# altiumDesignerSchematic.net
KiCad netlist of a schematic drawn in Altium Designer
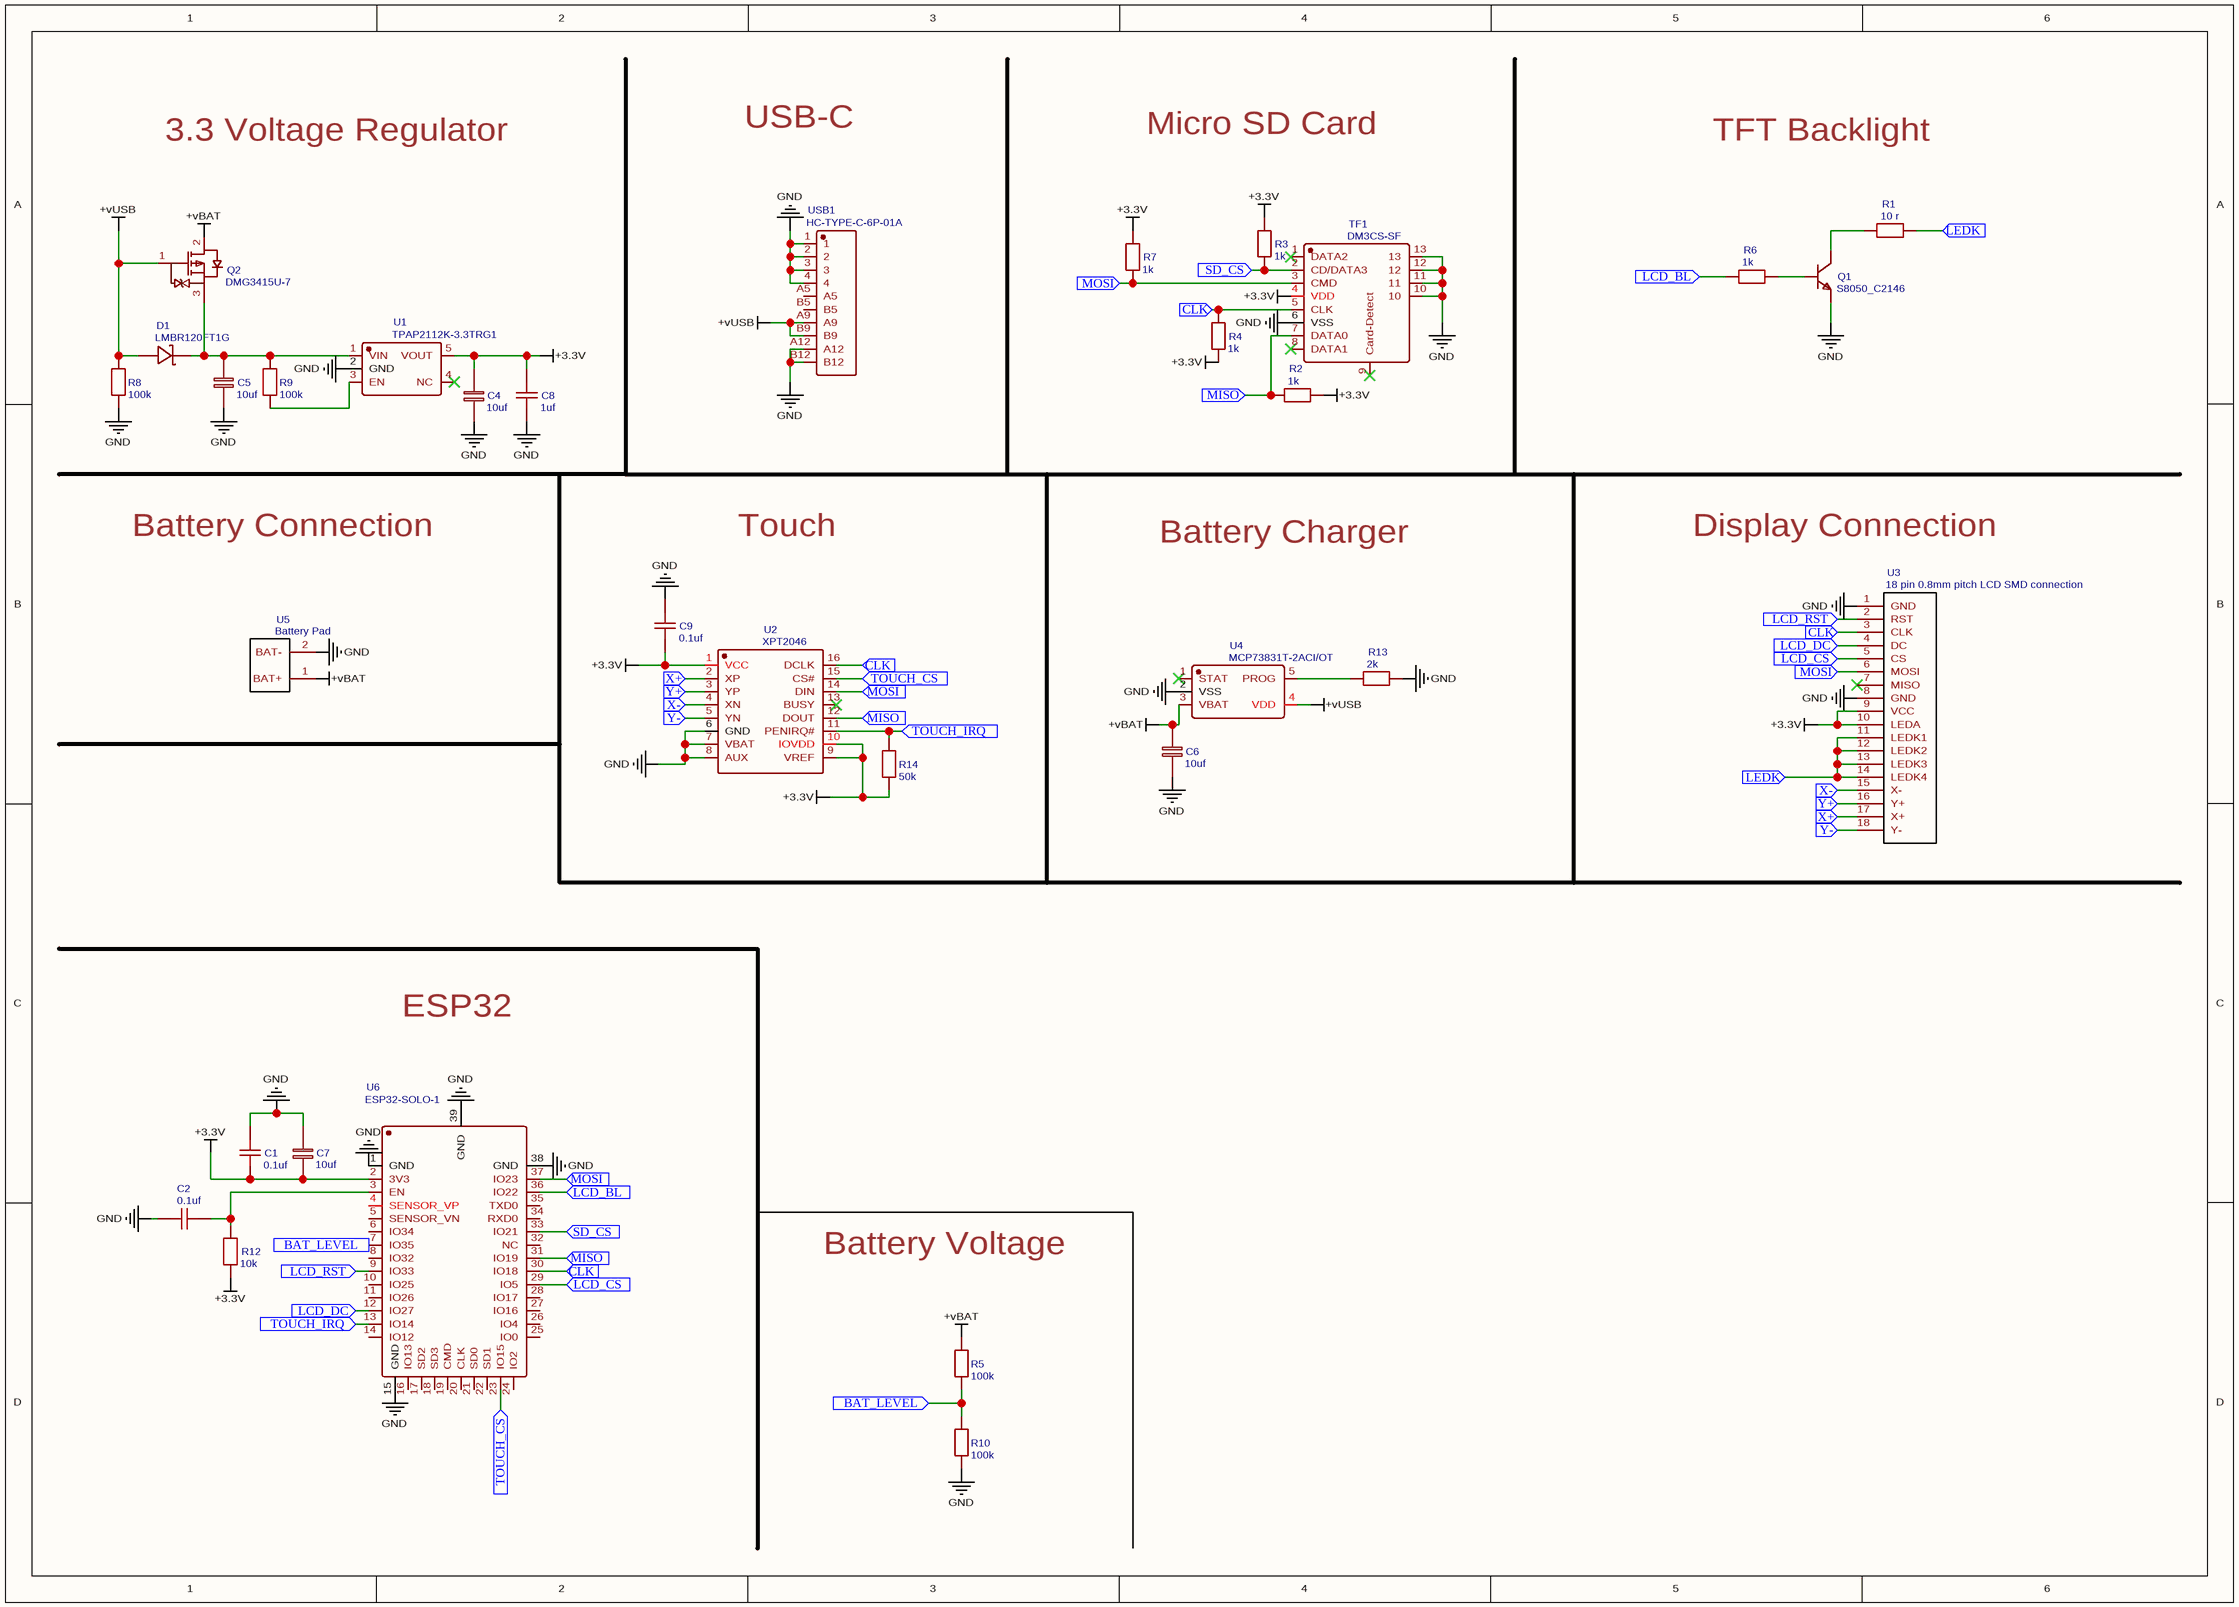
[diagram p0: altiumDesignerSchematic.schdoc]

(export (version "E")
  (design (tool "Eeschema 10.0.6"))
  (components
    (comp (ref "C1")
      (value "0.1uf")
      (fields (field (name "CONTRIBUTOR") "LCEDA_Lib"))
      (libsource (lib "altium-import") (part "root_1_0.1uf_"))
    )
    (comp (ref "C2")
      (value "0.1uf")
      (fields (field (name "CONTRIBUTOR") "LCEDA_Lib"))
      (libsource (lib "altium-import") (part "root_2_0.1uf_"))
    )
    (comp (ref "C4")
      (value "10uf")
      (fields (field (name "CONTRIBUTOR") "LCEDA_Lib"))
      (libsource (lib "altium-import") (part "root_1_10uf_"))
    )
    (comp (ref "C5")
      (value "10uf")
      (fields (field (name "CONTRIBUTOR") "LCEDA_Lib"))
      (libsource (lib "altium-import") (part "root_1_10uf_"))
    )
    (comp (ref "C6")
      (value "10uf")
      (fields (field (name "CONTRIBUTOR") "LCEDA_Lib"))
      (libsource (lib "altium-import") (part "root_1_10uf_"))
    )
    (comp (ref "C7")
      (value "10uf")
      (fields (field (name "CONTRIBUTOR") "LCEDA_Lib"))
      (libsource (lib "altium-import") (part "root_1_10uf_"))
    )
    (comp (ref "C8")
      (value "1uf")
      (fields (field (name "CONTRIBUTOR") "LCEDA_Lib"))
      (libsource (lib "altium-import") (part "root_1_1uf_"))
    )
    (comp (ref "C9")
      (value "0.1uf")
      (fields (field (name "CONTRIBUTOR") "LCEDA_Lib"))
      (libsource (lib "altium-import") (part "root_1_0.1uf_"))
    )
    (comp (ref "D1")
      (value "LMBR120FT1G")
      (fields (field (name "BOM_SUPPLIER PART") "C81143"))
      (libsource (lib "altium-import") (part "root_2_LMBR120FT1G_"))
    )
    (comp (ref "Q1")
      (value "S8050_C2146")
      (fields (field (name "BOM_MANUFACTURER PART") "S8050 J3Y") (field (name "BOM_SUPPLIER PART") "C2146"))
      (libsource (lib "altium-import") (part "root_0_S8050_C2146_"))
    )
    (comp (ref "Q2")
      (value "DMG3415U-7")
      (fields (field (name "BOM_SUPPLIER PART") "C96616") (field (name "CONTRIBUTOR") "LCSC"))
      (libsource (lib "altium-import") (part "root_0_DMG3415U-7_"))
    )
    (comp (ref "R1")
      (value "10 r")
      (fields (field (name "CONTRIBUTOR") "LCEDA_Lib"))
      (libsource (lib "altium-import") (part "root_0_10 r_"))
    )
    (comp (ref "R2")
      (value "1k")
      (fields (field (name "CONTRIBUTOR") "LCEDA_Lib"))
      (libsource (lib "altium-import") (part "root_0_1k_"))
    )
    (comp (ref "R3")
      (value "1k")
      (fields (field (name "CONTRIBUTOR") "LCEDA_Lib"))
      (libsource (lib "altium-import") (part "root_1_1k_"))
    )
    (comp (ref "R4")
      (value "1k")
      (fields (field (name "CONTRIBUTOR") "LCEDA_Lib"))
      (libsource (lib "altium-import") (part "root_1_1k_"))
    )
    (comp (ref "R5")
      (value "100k")
      (fields (field (name "CONTRIBUTOR") "LCEDA_Lib"))
      (libsource (lib "altium-import") (part "root_1_100k_"))
    )
    (comp (ref "R6")
      (value "1k")
      (fields (field (name "CONTRIBUTOR") "LCEDA_Lib"))
      (libsource (lib "altium-import") (part "root_0_1k_"))
    )
    (comp (ref "R7")
      (value "1k")
      (fields (field (name "CONTRIBUTOR") "LCEDA_Lib"))
      (libsource (lib "altium-import") (part "root_1_1k_"))
    )
    (comp (ref "R8")
      (value "100k")
      (fields (field (name "CONTRIBUTOR") "LCEDA_Lib"))
      (libsource (lib "altium-import") (part "root_1_100k_"))
    )
    (comp (ref "R9")
      (value "100k")
      (fields (field (name "CONTRIBUTOR") "LCEDA_Lib"))
      (libsource (lib "altium-import") (part "root_1_100k_"))
    )
    (comp (ref "R10")
      (value "100k")
      (fields (field (name "CONTRIBUTOR") "LCEDA_Lib"))
      (libsource (lib "altium-import") (part "root_1_100k_"))
    )
    (comp (ref "R12")
      (value "10k")
      (fields (field (name "CONTRIBUTOR") "LCEDA_Lib"))
      (libsource (lib "altium-import") (part "root_1_10k_"))
    )
    (comp (ref "R13")
      (value "2k")
      (fields (field (name "CONTRIBUTOR") "LCEDA_Lib"))
      (libsource (lib "altium-import") (part "root_0_2k_"))
    )
    (comp (ref "R14")
      (value "50k")
      (fields (field (name "CONTRIBUTOR") "LCEDA_Lib"))
      (libsource (lib "altium-import") (part "root_1_50k_"))
    )
    (comp (ref "TF1")
      (value "DM3CS-SF")
      (fields (field (name "BOM_SUPPLIER PART") "C202111") (field (name "CONTRIBUTOR") "LCSC"))
      (libsource (lib "altium-import") (part "root_0_DM3CS-SF_"))
    )
    (comp (ref "U1")
      (value "TPAP2112K-3.3TRG1")
      (fields (field (name "BOM_SUPPLIER PART") "C3021085") (field (name "CONTRIBUTOR") "lcsc"))
      (libsource (lib "altium-import") (part "root_0_TPAP2112K-3.3TRG1_"))
    )
    (comp (ref "U2")
      (value "XPT2046")
      (fields (field (name "BOM_SUPPLIER PART") "C19076"))
      (libsource (lib "altium-import") (part "root_0_XPT2046_"))
    )
    (comp (ref "U3")
      (value "18 pin 0.8mm pitch LCD SMD connection")
      (fields
        (field (name "BOM_MANUFACTURER PART") "spi tft screen generic 0.8mm pitch smd")
        (field (name "CONTRIBUTOR") "Jason Lashchuk")
      )
      (libsource (lib "altium-import") (part "root_0_18 pin 0.8mm pitch LCD SMD connection_"))
    )
    (comp (ref "U4")
      (value "MCP73831T-2ACI/OT")
      (fields (field (name "BOM_SUPPLIER PART") "C424093") (field (name "CONTRIBUTOR") "LCSC"))
      (libsource (lib "altium-import") (part "root_0_MCP73831T-2ACI/OT_"))
    )
    (comp (ref "U5")
      (value "Battery Pad")
      (fields (field (name "CONTRIBUTOR") "AshleeJ"))
      (libsource (lib "altium-import") (part "root_1_Battery Pad_"))
    )
    (comp (ref "U6")
      (value "ESP32-SOLO-1")
      (fields (field (name "BOM_SUPPLIER PART") "C473005") (field (name "CONTRIBUTOR") "LCSC"))
      (libsource (lib "altium-import") (part "root_0_ESP32-SOLO-1_"))
    )
    (comp (ref "USB1")
      (value "HC-TYPE-C-6P-01A")
      (fields (field (name "BOM_SUPPLIER PART") "C2894893") (field (name "CONTRIBUTOR") "LCSC"))
      (libsource (lib "altium-import") (part "root_0_HC-TYPE-C-6P-01A_"))
    )
  )
  (nets
    (net (code "1") (name "+3.3V") (class "Default")
      (node (ref "C1") (pin "1") (pinfunction "1_1") (pintype "passive"))
      (node (ref "C4") (pin "2") (pinfunction "2_2") (pintype "passive"))
      (node (ref "C7") (pin "1") (pinfunction "1_1") (pintype "passive"))
      (node (ref "C8") (pin "2") (pinfunction "2_2") (pintype "passive"))
      (node (ref "C9") (pin "1") (pinfunction "1_1") (pintype "passive"))
      (node (ref "R12") (pin "1") (pinfunction "1_1") (pintype "passive"))
      (node (ref "R14") (pin "1") (pinfunction "1_1") (pintype "passive"))
      (node (ref "R2") (pin "2") (pinfunction "2_2") (pintype "passive"))
      (node (ref "R3") (pin "2") (pinfunction "2_2") (pintype "passive"))
      (node (ref "R4") (pin "1") (pinfunction "1_1") (pintype "passive"))
      (node (ref "R7") (pin "2") (pinfunction "2_2") (pintype "passive"))
      (node (ref "TF1") (pin "4") (pinfunction "VDD_4") (pintype "passive"))
      (node (ref "U1") (pin "5") (pinfunction "VOUT_5") (pintype "passive"))
      (node (ref "U2") (pin "1") (pinfunction "VCC_1") (pintype "passive"))
      (node (ref "U2") (pin "10") (pinfunction "IOVDD_10") (pintype "passive"))
      (node (ref "U2") (pin "9") (pinfunction "VREF_9") (pintype "passive"))
      (node (ref "U3") (pin "10") (pinfunction "LEDA_10") (pintype "passive"))
      (node (ref "U3") (pin "9") (pinfunction "VCC_9") (pintype "passive"))
      (node (ref "U6") (pin "2") (pinfunction "3V3_2") (pintype "passive"))
    )
    (net (code "2") (name "+vBAT") (class "Default")
      (node (ref "C6") (pin "2") (pinfunction "2_2") (pintype "passive"))
      (node (ref "Q2") (pin "2") (pinfunction "D_2") (pintype "passive"))
      (node (ref "R5") (pin "2") (pinfunction "2_2") (pintype "passive"))
      (node (ref "U4") (pin "3") (pinfunction "VBAT_3") (pintype "passive"))
      (node (ref "U5") (pin "1") (pinfunction "BAT+_1") (pintype "passive"))
    )
    (net (code "3") (name "+vUSB") (class "Default")
      (node (ref "D1") (pin "2") (pinfunction "A_2") (pintype "passive"))
      (node (ref "Q2") (pin "1") (pinfunction "G_1") (pintype "passive"))
      (node (ref "R8") (pin "2") (pinfunction "2_2") (pintype "passive"))
      (node (ref "U4") (pin "4") (pinfunction "VDD_4") (pintype "passive"))
      (node (ref "USB1") (pin "A9") (pinfunction "A9_A9") (pintype "passive"))
      (node (ref "USB1") (pin "B9") (pinfunction "B9_B9") (pintype "passive"))
    )
    (net (code "4") (name "/BAT_LEVEL") (class "Default")
      (node (ref "R10") (pin "2") (pinfunction "2_2") (pintype "passive"))
      (node (ref "R5") (pin "1") (pinfunction "1_1") (pintype "passive"))
      (node (ref "U6") (pin "7") (pinfunction "IO35_7") (pintype "passive"))
    )
    (net (code "5") (name "/CLK") (class "Default")
      (node (ref "R4") (pin "2") (pinfunction "2_2") (pintype "passive"))
      (node (ref "TF1") (pin "5") (pinfunction "CLK_5") (pintype "passive"))
      (node (ref "U2") (pin "16") (pinfunction "DCLK_16") (pintype "passive"))
      (node (ref "U3") (pin "3") (pinfunction "CLK_3") (pintype "passive"))
      (node (ref "U6") (pin "30") (pinfunction "IO18_30") (pintype "passive"))
    )
    (net (code "6") (name "/LCD_BL") (class "Default")
      (node (ref "R6") (pin "1") (pinfunction "1_1") (pintype "passive"))
      (node (ref "U6") (pin "36") (pinfunction "IO22_36") (pintype "passive"))
    )
    (net (code "7") (name "/LCD_CS") (class "Default")
      (node (ref "U3") (pin "5") (pinfunction "CS_5") (pintype "passive"))
      (node (ref "U6") (pin "29") (pinfunction "IO5_29") (pintype "passive"))
    )
    (net (code "8") (name "/LCD_DC") (class "Default")
      (node (ref "U3") (pin "4") (pinfunction "DC_4") (pintype "passive"))
      (node (ref "U6") (pin "12") (pinfunction "IO27_12") (pintype "passive"))
    )
    (net (code "9") (name "/LCD_RST") (class "Default")
      (node (ref "U3") (pin "2") (pinfunction "RST_2") (pintype "passive"))
      (node (ref "U6") (pin "9") (pinfunction "IO33_9") (pintype "passive"))
    )
    (net (code "10") (name "/LEDK") (class "Default")
      (node (ref "R1") (pin "2") (pinfunction "2_2") (pintype "passive"))
      (node (ref "U3") (pin "11") (pinfunction "LEDK1_11") (pintype "passive"))
      (node (ref "U3") (pin "12") (pinfunction "LEDK2_12") (pintype "passive"))
      (node (ref "U3") (pin "13") (pinfunction "LEDK3_13") (pintype "passive"))
      (node (ref "U3") (pin "14") (pinfunction "LEDK4_14") (pintype "passive"))
    )
    (net (code "11") (name "/MISO") (class "Default")
      (node (ref "R2") (pin "1") (pinfunction "1_1") (pintype "passive"))
      (node (ref "TF1") (pin "7") (pinfunction "DATA0_7") (pintype "passive"))
      (node (ref "U2") (pin "12") (pinfunction "DOUT_12") (pintype "passive"))
      (node (ref "U6") (pin "31") (pinfunction "IO19_31") (pintype "passive"))
    )
    (net (code "12") (name "/MOSI") (class "Default")
      (node (ref "R7") (pin "1") (pinfunction "1_1") (pintype "passive"))
      (node (ref "TF1") (pin "3") (pinfunction "CMD_3") (pintype "passive"))
      (node (ref "U2") (pin "14") (pinfunction "DIN_14") (pintype "passive"))
      (node (ref "U3") (pin "6") (pinfunction "MOSI_6") (pintype "passive"))
      (node (ref "U6") (pin "37") (pinfunction "IO23_37") (pintype "passive"))
    )
    (net (code "13") (name "/SD_CS") (class "Default")
      (node (ref "R3") (pin "1") (pinfunction "1_1") (pintype "passive"))
      (node (ref "TF1") (pin "2") (pinfunction "CD/DATA3_2") (pintype "passive"))
      (node (ref "U6") (pin "33") (pinfunction "IO21_33") (pintype "passive"))
    )
    (net (code "14") (name "/TOUCH_CS") (class "Default")
      (node (ref "U2") (pin "15") (pinfunction "CS#_15") (pintype "passive"))
      (node (ref "U6") (pin "23") (pinfunction "IO15_23") (pintype "passive"))
    )
    (net (code "15") (name "/TOUCH_IRQ") (class "Default")
      (node (ref "R14") (pin "2") (pinfunction "2_2") (pintype "passive"))
      (node (ref "U2") (pin "11") (pinfunction "PENIRQ#_11") (pintype "passive"))
      (node (ref "U6") (pin "13") (pinfunction "IO14_13") (pintype "passive"))
    )
    (net (code "16") (name "/X+") (class "Default")
      (node (ref "U2") (pin "2") (pinfunction "XP_2") (pintype "passive"))
      (node (ref "U3") (pin "17") (pinfunction "X+_17") (pintype "passive"))
    )
    (net (code "17") (name "/X-") (class "Default")
      (node (ref "U2") (pin "4") (pinfunction "XN_4") (pintype "passive"))
      (node (ref "U3") (pin "15") (pinfunction "X-_15") (pintype "passive"))
    )
    (net (code "18") (name "/Y+") (class "Default")
      (node (ref "U2") (pin "3") (pinfunction "YP_3") (pintype "passive"))
      (node (ref "U3") (pin "16") (pinfunction "Y+_16") (pintype "passive"))
    )
    (net (code "19") (name "/Y-") (class "Default")
      (node (ref "U2") (pin "5") (pinfunction "YN_5") (pintype "passive"))
      (node (ref "U3") (pin "18") (pinfunction "Y-_18") (pintype "passive"))
    )
    (net (code "20") (name "GND") (class "Default")
      (node (ref "C1") (pin "2") (pinfunction "2_2") (pintype "passive"))
      (node (ref "C2") (pin "2") (pinfunction "2_2") (pintype "passive"))
      (node (ref "C4") (pin "1") (pinfunction "1_1") (pintype "passive"))
      (node (ref "C5") (pin "1") (pinfunction "1_1") (pintype "passive"))
      (node (ref "C6") (pin "1") (pinfunction "1_1") (pintype "passive"))
      (node (ref "C7") (pin "2") (pinfunction "2_2") (pintype "passive"))
      (node (ref "C8") (pin "1") (pinfunction "1_1") (pintype "passive"))
      (node (ref "C9") (pin "2") (pinfunction "2_2") (pintype "passive"))
      (node (ref "Q1") (pin "2") (pinfunction "E_2") (pintype "passive"))
      (node (ref "R10") (pin "1") (pinfunction "1_1") (pintype "passive"))
      (node (ref "R13") (pin "2") (pinfunction "2_2") (pintype "passive"))
      (node (ref "R8") (pin "1") (pinfunction "1_1") (pintype "passive"))
      (node (ref "TF1") (pin "10") (pinfunction "10_10") (pintype "passive"))
      (node (ref "TF1") (pin "11") (pinfunction "11_11") (pintype "passive"))
      (node (ref "TF1") (pin "12") (pinfunction "12_12") (pintype "passive"))
      (node (ref "TF1") (pin "13") (pinfunction "13_13") (pintype "passive"))
      (node (ref "TF1") (pin "6") (pinfunction "VSS_6") (pintype "passive"))
      (node (ref "U1") (pin "2") (pinfunction "GND_2") (pintype "passive"))
      (node (ref "U2") (pin "6") (pinfunction "GND_6") (pintype "passive"))
      (node (ref "U2") (pin "7") (pinfunction "VBAT_7") (pintype "passive"))
      (node (ref "U2") (pin "8") (pinfunction "AUX_8") (pintype "passive"))
      (node (ref "U3") (pin "1") (pinfunction "GND_1") (pintype "passive"))
      (node (ref "U3") (pin "8") (pinfunction "GND_8") (pintype "passive"))
      (node (ref "U4") (pin "2") (pinfunction "VSS_2") (pintype "passive"))
      (node (ref "U5") (pin "2") (pinfunction "BAT-_2") (pintype "passive"))
      (node (ref "U6") (pin "1") (pinfunction "GND_1") (pintype "passive"))
      (node (ref "U6") (pin "15") (pinfunction "GND_15") (pintype "passive"))
      (node (ref "U6") (pin "38") (pinfunction "GND_38") (pintype "passive"))
      (node (ref "U6") (pin "39") (pinfunction "GND_39") (pintype "passive"))
      (node (ref "USB1") (pin "1") (pinfunction "1_1") (pintype "passive"))
      (node (ref "USB1") (pin "2") (pinfunction "2_2") (pintype "passive"))
      (node (ref "USB1") (pin "3") (pinfunction "3_3") (pintype "passive"))
      (node (ref "USB1") (pin "4") (pinfunction "4_4") (pintype "passive"))
      (node (ref "USB1") (pin "A12") (pinfunction "A12_A12") (pintype "passive"))
      (node (ref "USB1") (pin "B12") (pinfunction "B12_B12") (pintype "passive"))
    )
    (net (code "21") (name "Net-(D1-K)") (class "Default")
      (node (ref "C5") (pin "2") (pinfunction "2_2") (pintype "passive"))
      (node (ref "D1") (pin "1") (pinfunction "K_1") (pintype "passive"))
      (node (ref "Q2") (pin "3") (pinfunction "S_3") (pintype "passive"))
      (node (ref "R9") (pin "2") (pinfunction "2_2") (pintype "passive"))
      (node (ref "U1") (pin "1") (pinfunction "VIN_1") (pintype "passive"))
    )
    (net (code "22") (name "Net-(Q1-B)") (class "Default")
      (node (ref "Q1") (pin "1") (pinfunction "B_1") (pintype "passive"))
      (node (ref "R6") (pin "2") (pinfunction "2_2") (pintype "passive"))
    )
    (net (code "23") (name "Net-(Q1-C)") (class "Default")
      (node (ref "Q1") (pin "3") (pinfunction "C_3") (pintype "passive"))
      (node (ref "R1") (pin "1") (pinfunction "1_1") (pintype "passive"))
    )
    (net (code "24") (name "Net-(U1-EN)") (class "Default")
      (node (ref "R9") (pin "1") (pinfunction "1_1") (pintype "passive"))
      (node (ref "U1") (pin "3") (pinfunction "EN_3") (pintype "passive"))
    )
    (net (code "25") (name "Net-(U4-PROG)") (class "Default")
      (node (ref "R13") (pin "1") (pinfunction "1_1") (pintype "passive"))
      (node (ref "U4") (pin "5") (pinfunction "PROG_5") (pintype "passive"))
    )
    (net (code "26") (name "Net-(U6-EN)") (class "Default")
      (node (ref "C2") (pin "1") (pinfunction "1_1") (pintype "passive"))
      (node (ref "R12") (pin "2") (pinfunction "2_2") (pintype "passive"))
      (node (ref "U6") (pin "3") (pinfunction "EN_3") (pintype "passive"))
    )
    (net (code "27") (name "unconnected-(TF1-Card-Detect-Pad9)") (class "Default")
      (node (ref "TF1") (pin "9") (pinfunction "Card-Detect_9") (pintype "passive+no_connect"))
    )
    (net (code "28") (name "unconnected-(TF1-DATA1-Pad8)") (class "Default")
      (node (ref "TF1") (pin "8") (pinfunction "DATA1_8") (pintype "passive+no_connect"))
    )
    (net (code "29") (name "unconnected-(TF1-DATA2-Pad1)") (class "Default")
      (node (ref "TF1") (pin "1") (pinfunction "DATA2_1") (pintype "passive+no_connect"))
    )
    (net (code "30") (name "unconnected-(U1-NC-Pad4)") (class "Default")
      (node (ref "U1") (pin "4") (pinfunction "NC_4") (pintype "passive+no_connect"))
    )
    (net (code "31") (name "unconnected-(U2-BUSY-Pad13)") (class "Default")
      (node (ref "U2") (pin "13") (pinfunction "BUSY_13") (pintype "passive+no_connect"))
    )
    (net (code "32") (name "unconnected-(U3-MISO-Pad7)") (class "Default")
      (node (ref "U3") (pin "7") (pinfunction "MISO_7") (pintype "passive+no_connect"))
    )
    (net (code "33") (name "unconnected-(U4-STAT-Pad1)") (class "Default")
      (node (ref "U4") (pin "1") (pinfunction "STAT_1") (pintype "passive+no_connect"))
    )
    (net (code "34") (name "unconnected-(U6-CLK-Pad20)") (class "Default")
      (node (ref "U6") (pin "20") (pinfunction "CLK_20") (pintype "passive"))
    )
    (net (code "35") (name "unconnected-(U6-CMD-Pad19)") (class "Default")
      (node (ref "U6") (pin "19") (pinfunction "CMD_19") (pintype "passive"))
    )
    (net (code "36") (name "unconnected-(U6-IO0-Pad25)") (class "Default")
      (node (ref "U6") (pin "25") (pinfunction "IO0_25") (pintype "passive"))
    )
    (net (code "37") (name "unconnected-(U6-IO2-Pad24)") (class "Default")
      (node (ref "U6") (pin "24") (pinfunction "IO2_24") (pintype "passive"))
    )
    (net (code "38") (name "unconnected-(U6-IO4-Pad26)") (class "Default")
      (node (ref "U6") (pin "26") (pinfunction "IO4_26") (pintype "passive"))
    )
    (net (code "39") (name "unconnected-(U6-IO12-Pad14)") (class "Default")
      (node (ref "U6") (pin "14") (pinfunction "IO12_14") (pintype "passive"))
    )
    (net (code "40") (name "unconnected-(U6-IO13-Pad16)") (class "Default")
      (node (ref "U6") (pin "16") (pinfunction "IO13_16") (pintype "passive"))
    )
    (net (code "41") (name "unconnected-(U6-IO16-Pad27)") (class "Default")
      (node (ref "U6") (pin "27") (pinfunction "IO16_27") (pintype "passive"))
    )
    (net (code "42") (name "unconnected-(U6-IO17-Pad28)") (class "Default")
      (node (ref "U6") (pin "28") (pinfunction "IO17_28") (pintype "passive"))
    )
    (net (code "43") (name "unconnected-(U6-IO25-Pad10)") (class "Default")
      (node (ref "U6") (pin "10") (pinfunction "IO25_10") (pintype "passive"))
    )
    (net (code "44") (name "unconnected-(U6-IO26-Pad11)") (class "Default")
      (node (ref "U6") (pin "11") (pinfunction "IO26_11") (pintype "passive"))
    )
    (net (code "45") (name "unconnected-(U6-IO32-Pad8)") (class "Default")
      (node (ref "U6") (pin "8") (pinfunction "IO32_8") (pintype "passive"))
    )
    (net (code "46") (name "unconnected-(U6-IO34-Pad6)") (class "Default")
      (node (ref "U6") (pin "6") (pinfunction "IO34_6") (pintype "passive"))
    )
    (net (code "47") (name "unconnected-(U6-NC-Pad32)") (class "Default")
      (node (ref "U6") (pin "32") (pinfunction "NC_32") (pintype "passive"))
    )
    (net (code "48") (name "unconnected-(U6-RXD0-Pad34)") (class "Default")
      (node (ref "U6") (pin "34") (pinfunction "RXD0_34") (pintype "passive"))
    )
    (net (code "49") (name "unconnected-(U6-SD0-Pad21)") (class "Default")
      (node (ref "U6") (pin "21") (pinfunction "SD0_21") (pintype "passive"))
    )
    (net (code "50") (name "unconnected-(U6-SD1-Pad22)") (class "Default")
      (node (ref "U6") (pin "22") (pinfunction "SD1_22") (pintype "passive"))
    )
    (net (code "51") (name "unconnected-(U6-SD2-Pad17)") (class "Default")
      (node (ref "U6") (pin "17") (pinfunction "SD2_17") (pintype "passive"))
    )
    (net (code "52") (name "unconnected-(U6-SD3-Pad18)") (class "Default")
      (node (ref "U6") (pin "18") (pinfunction "SD3_18") (pintype "passive"))
    )
    (net (code "53") (name "unconnected-(U6-SENSOR_VN-Pad5)") (class "Default")
      (node (ref "U6") (pin "5") (pinfunction "SENSOR_VN_5") (pintype "passive"))
    )
    (net (code "54") (name "unconnected-(U6-SENSOR_VP-Pad4)") (class "Default")
      (node (ref "U6") (pin "4") (pinfunction "SENSOR_VP_4") (pintype "passive"))
    )
    (net (code "55") (name "unconnected-(U6-TXD0-Pad35)") (class "Default")
      (node (ref "U6") (pin "35") (pinfunction "TXD0_35") (pintype "passive"))
    )
    (net (code "56") (name "unconnected-(USB1-PadA5)") (class "Default")
      (node (ref "USB1") (pin "A5") (pinfunction "A5_A5") (pintype "passive"))
    )
    (net (code "57") (name "unconnected-(USB1-PadB5)") (class "Default")
      (node (ref "USB1") (pin "B5") (pinfunction "B5_B5") (pintype "passive"))
    )
  )
)
